# radiata_v2.net
KiCad netlist of a schematic drawn in EAGLE
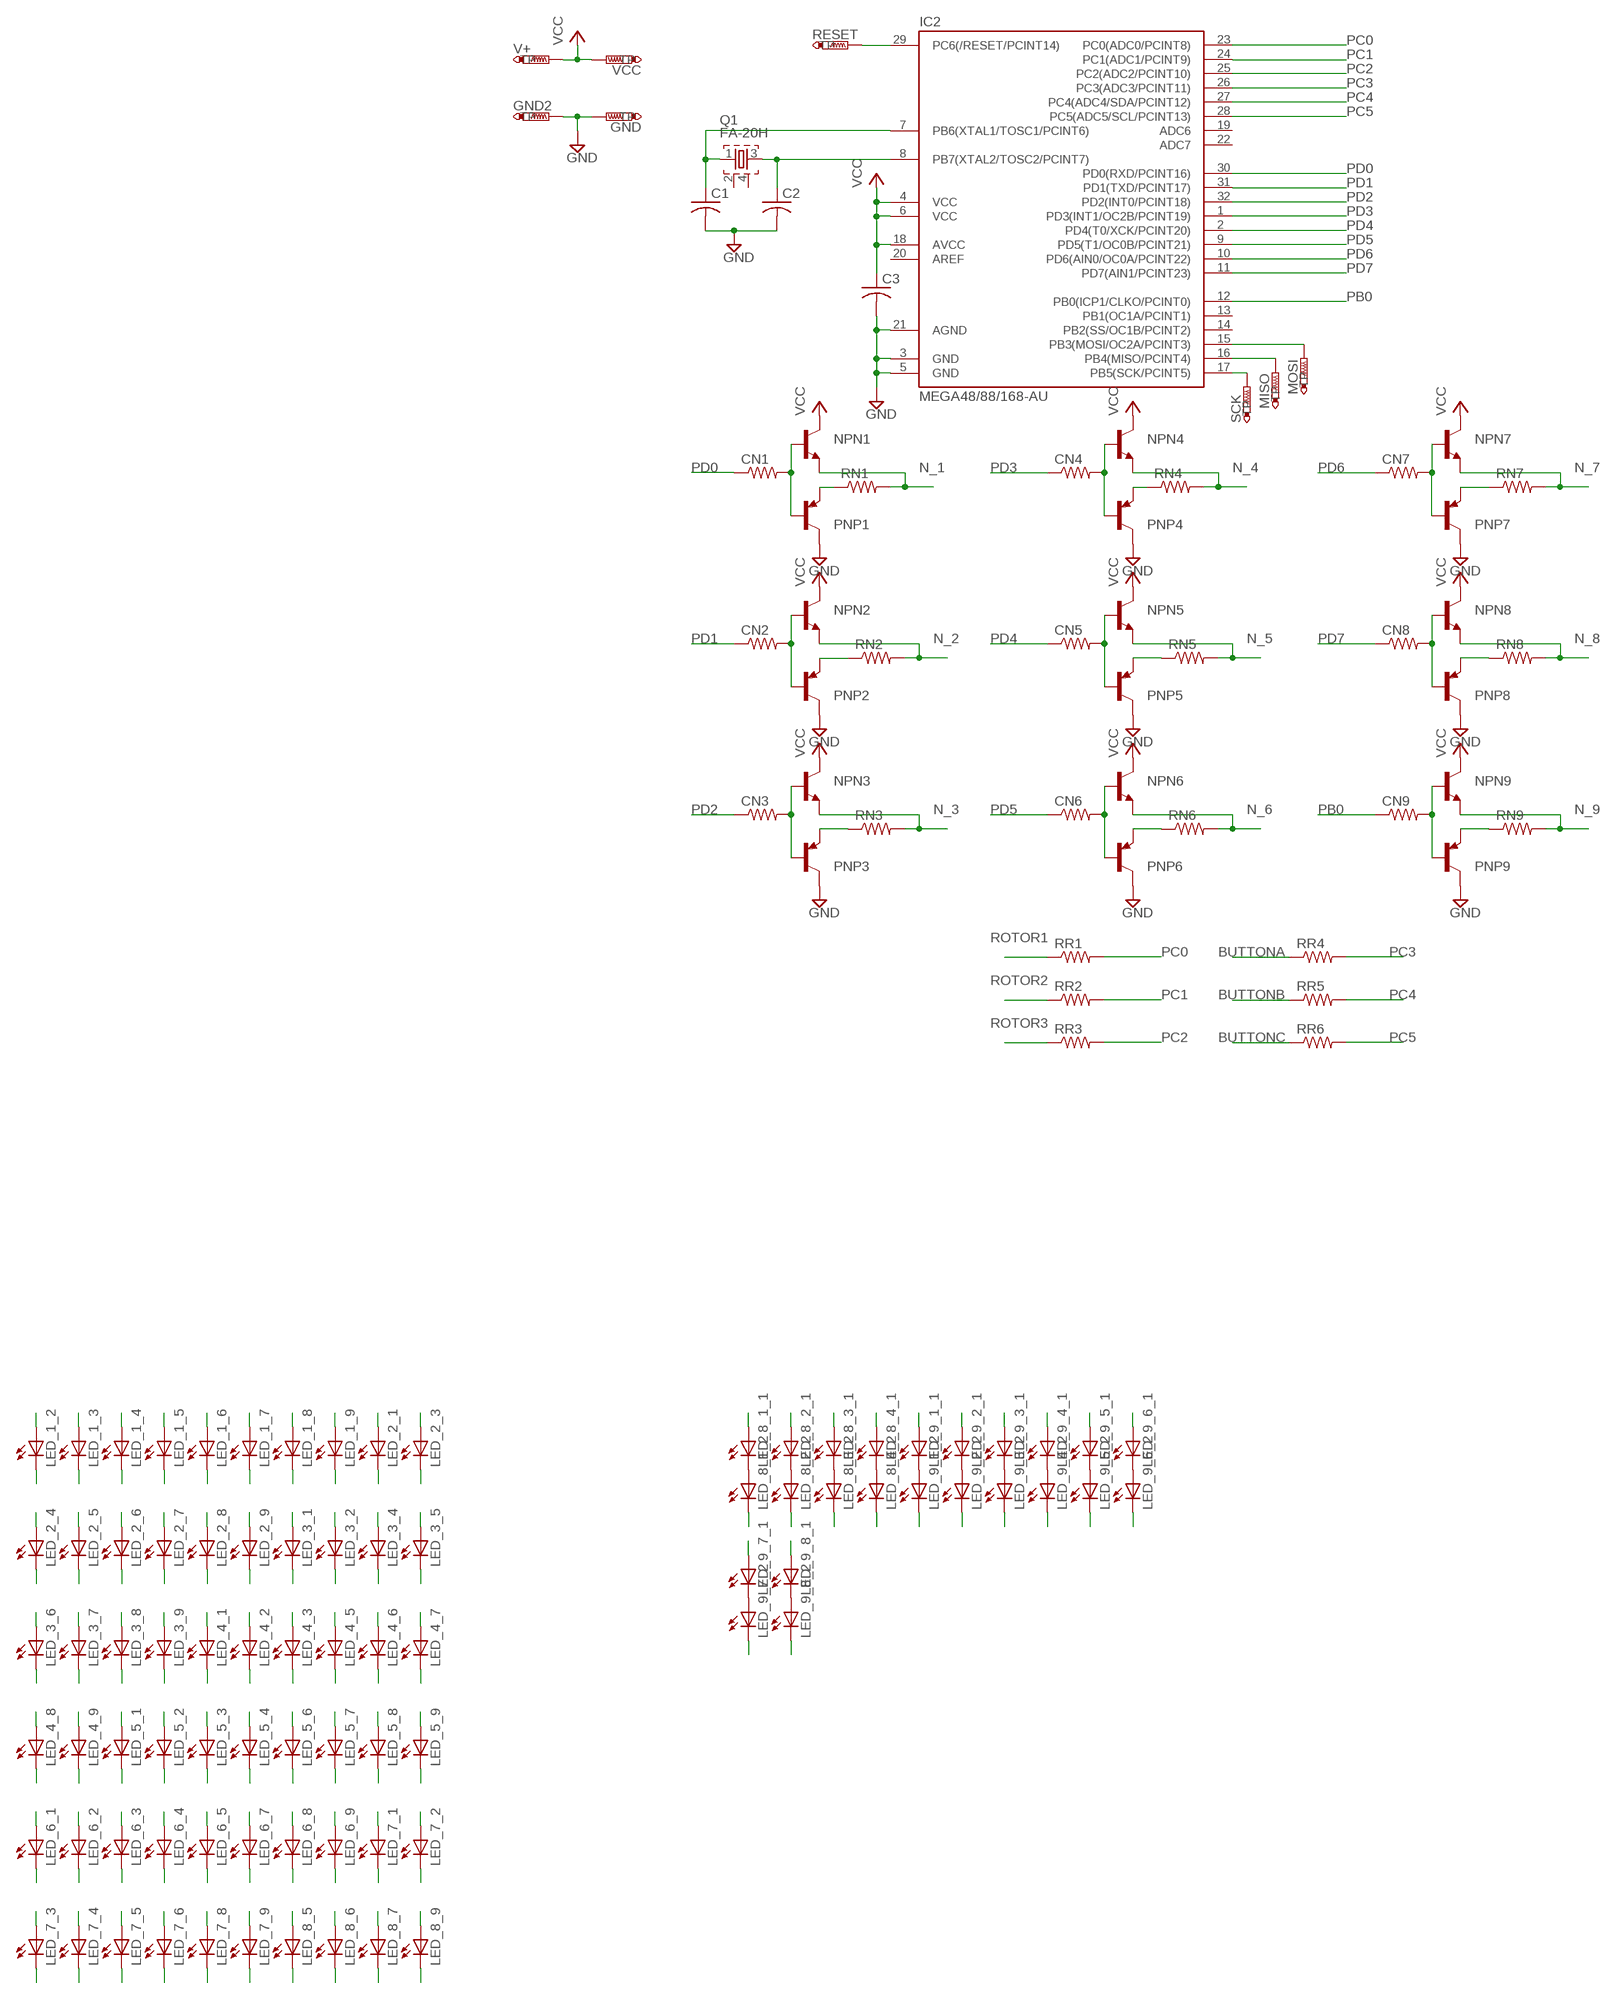
[diagram p0: schematic, sheet 1]

(export (version "E")
  (design (tool "Eeschema 10.0.6"))
  (components
    (comp (ref "C1")
      (value "C-USC0603")
      (footprint "eagle-import:C0603")
      (libsource (lib "eagle-import") (part "C-USC0603"))
    )
    (comp (ref "C2")
      (value "C-USC0603")
      (footprint "eagle-import:C0603")
      (libsource (lib "eagle-import") (part "C-USC0603"))
    )
    (comp (ref "C3")
      (value "C-USC0603")
      (footprint "eagle-import:C0603")
      (libsource (lib "eagle-import") (part "C-USC0603"))
    )
    (comp (ref "CN1")
      (value "R-US_M0805")
      (footprint "eagle-import:M0805")
      (libsource (lib "eagle-import") (part "R-US_M0805"))
    )
    (comp (ref "CN2")
      (value "R-US_M0805")
      (footprint "eagle-import:M0805")
      (libsource (lib "eagle-import") (part "R-US_M0805"))
    )
    (comp (ref "CN3")
      (value "R-US_M0805")
      (footprint "eagle-import:M0805")
      (libsource (lib "eagle-import") (part "R-US_M0805"))
    )
    (comp (ref "CN4")
      (value "R-US_M0805")
      (footprint "eagle-import:M0805")
      (libsource (lib "eagle-import") (part "R-US_M0805"))
    )
    (comp (ref "CN5")
      (value "R-US_M0805")
      (footprint "eagle-import:M0805")
      (libsource (lib "eagle-import") (part "R-US_M0805"))
    )
    (comp (ref "CN6")
      (value "R-US_M0805")
      (footprint "eagle-import:M0805")
      (libsource (lib "eagle-import") (part "R-US_M0805"))
    )
    (comp (ref "CN7")
      (value "R-US_M0805")
      (footprint "eagle-import:M0805")
      (libsource (lib "eagle-import") (part "R-US_M0805"))
    )
    (comp (ref "CN8")
      (value "R-US_M0805")
      (footprint "eagle-import:M0805")
      (libsource (lib "eagle-import") (part "R-US_M0805"))
    )
    (comp (ref "CN9")
      (value "R-US_M0805")
      (footprint "eagle-import:M0805")
      (libsource (lib "eagle-import") (part "R-US_M0805"))
    )
    (comp (ref "GND")
      (value "PTR1TP19R")
      (footprint "eagle-import:TP19R")
      (libsource (lib "eagle-import") (part "PTR1TP19R"))
    )
    (comp (ref "GND2")
      (value "PTR1TP20SQ")
      (footprint "eagle-import:TP20SQ")
      (libsource (lib "eagle-import") (part "PTR1TP20SQ"))
    )
    (comp (ref "IC2")
      (value "MEGA48/88/168-AU")
      (footprint "eagle-import:TQFP32-08")
      (libsource (lib "eagle-import") (part "MEGA48/88/168-AU"))
    )
    (comp (ref "LED_1_2")
      (value "LED1206")
      (footprint "eagle-import:LED-1206")
      (libsource (lib "eagle-import") (part "LED1206"))
    )
    (comp (ref "LED_1_3")
      (value "LED1206")
      (footprint "eagle-import:LED-1206")
      (libsource (lib "eagle-import") (part "LED1206"))
    )
    (comp (ref "LED_1_4")
      (value "LED1206")
      (footprint "eagle-import:LED-1206")
      (libsource (lib "eagle-import") (part "LED1206"))
    )
    (comp (ref "LED_1_5")
      (value "LED1206")
      (footprint "eagle-import:LED-1206")
      (libsource (lib "eagle-import") (part "LED1206"))
    )
    (comp (ref "LED_1_6")
      (value "LED1206")
      (footprint "eagle-import:LED-1206")
      (libsource (lib "eagle-import") (part "LED1206"))
    )
    (comp (ref "LED_1_7")
      (value "LED1206")
      (footprint "eagle-import:LED-1206")
      (libsource (lib "eagle-import") (part "LED1206"))
    )
    (comp (ref "LED_1_8")
      (value "LED1206")
      (footprint "eagle-import:LED-1206")
      (libsource (lib "eagle-import") (part "LED1206"))
    )
    (comp (ref "LED_1_9")
      (value "LED1206")
      (footprint "eagle-import:LED-1206")
      (libsource (lib "eagle-import") (part "LED1206"))
    )
    (comp (ref "LED_2_1")
      (value "LED1206")
      (footprint "eagle-import:LED-1206")
      (libsource (lib "eagle-import") (part "LED1206"))
    )
    (comp (ref "LED_2_3")
      (value "LED1206")
      (footprint "eagle-import:LED-1206")
      (libsource (lib "eagle-import") (part "LED1206"))
    )
    (comp (ref "LED_2_4")
      (value "LED1206")
      (footprint "eagle-import:LED-1206")
      (libsource (lib "eagle-import") (part "LED1206"))
    )
    (comp (ref "LED_2_5")
      (value "LED1206")
      (footprint "eagle-import:LED-1206")
      (libsource (lib "eagle-import") (part "LED1206"))
    )
    (comp (ref "LED_2_6")
      (value "LED1206")
      (footprint "eagle-import:LED-1206")
      (libsource (lib "eagle-import") (part "LED1206"))
    )
    (comp (ref "LED_2_7")
      (value "LED1206")
      (footprint "eagle-import:LED-1206")
      (libsource (lib "eagle-import") (part "LED1206"))
    )
    (comp (ref "LED_2_8")
      (value "LED1206")
      (footprint "eagle-import:LED-1206")
      (libsource (lib "eagle-import") (part "LED1206"))
    )
    (comp (ref "LED_2_9")
      (value "LED1206")
      (footprint "eagle-import:LED-1206")
      (libsource (lib "eagle-import") (part "LED1206"))
    )
    (comp (ref "LED_3_1")
      (value "LED1206")
      (footprint "eagle-import:LED-1206")
      (libsource (lib "eagle-import") (part "LED1206"))
    )
    (comp (ref "LED_3_2")
      (value "LED1206")
      (footprint "eagle-import:LED-1206")
      (libsource (lib "eagle-import") (part "LED1206"))
    )
    (comp (ref "LED_3_4")
      (value "LED1206")
      (footprint "eagle-import:LED-1206")
      (libsource (lib "eagle-import") (part "LED1206"))
    )
    (comp (ref "LED_3_5")
      (value "LED1206")
      (footprint "eagle-import:LED-1206")
      (libsource (lib "eagle-import") (part "LED1206"))
    )
    (comp (ref "LED_3_6")
      (value "LED1206")
      (footprint "eagle-import:LED-1206")
      (libsource (lib "eagle-import") (part "LED1206"))
    )
    (comp (ref "LED_3_7")
      (value "LED1206")
      (footprint "eagle-import:LED-1206")
      (libsource (lib "eagle-import") (part "LED1206"))
    )
    (comp (ref "LED_3_8")
      (value "LED1206")
      (footprint "eagle-import:LED-1206")
      (libsource (lib "eagle-import") (part "LED1206"))
    )
    (comp (ref "LED_3_9")
      (value "LED1206")
      (footprint "eagle-import:LED-1206")
      (libsource (lib "eagle-import") (part "LED1206"))
    )
    (comp (ref "LED_4_1")
      (value "LED1206")
      (footprint "eagle-import:LED-1206")
      (libsource (lib "eagle-import") (part "LED1206"))
    )
    (comp (ref "LED_4_2")
      (value "LED1206")
      (footprint "eagle-import:LED-1206")
      (libsource (lib "eagle-import") (part "LED1206"))
    )
    (comp (ref "LED_4_3")
      (value "LED1206")
      (footprint "eagle-import:LED-1206")
      (libsource (lib "eagle-import") (part "LED1206"))
    )
    (comp (ref "LED_4_5")
      (value "LED1206")
      (footprint "eagle-import:LED-1206")
      (libsource (lib "eagle-import") (part "LED1206"))
    )
    (comp (ref "LED_4_6")
      (value "LED1206")
      (footprint "eagle-import:LED-1206")
      (libsource (lib "eagle-import") (part "LED1206"))
    )
    (comp (ref "LED_4_7")
      (value "LED1206")
      (footprint "eagle-import:LED-1206")
      (libsource (lib "eagle-import") (part "LED1206"))
    )
    (comp (ref "LED_4_8")
      (value "LED1206")
      (footprint "eagle-import:LED-1206")
      (libsource (lib "eagle-import") (part "LED1206"))
    )
    (comp (ref "LED_4_9")
      (value "LED1206")
      (footprint "eagle-import:LED-1206")
      (libsource (lib "eagle-import") (part "LED1206"))
    )
    (comp (ref "LED_5_1")
      (value "LED1206")
      (footprint "eagle-import:LED-1206")
      (libsource (lib "eagle-import") (part "LED1206"))
    )
    (comp (ref "LED_5_2")
      (value "LED1206")
      (footprint "eagle-import:LED-1206")
      (libsource (lib "eagle-import") (part "LED1206"))
    )
    (comp (ref "LED_5_3")
      (value "LED1206")
      (footprint "eagle-import:LED-1206")
      (libsource (lib "eagle-import") (part "LED1206"))
    )
    (comp (ref "LED_5_4")
      (value "LED1206")
      (footprint "eagle-import:LED-1206")
      (libsource (lib "eagle-import") (part "LED1206"))
    )
    (comp (ref "LED_5_6")
      (value "LED1206")
      (footprint "eagle-import:LED-1206")
      (libsource (lib "eagle-import") (part "LED1206"))
    )
    (comp (ref "LED_5_7")
      (value "LED1206")
      (footprint "eagle-import:LED-1206")
      (libsource (lib "eagle-import") (part "LED1206"))
    )
    (comp (ref "LED_5_8")
      (value "LED1206")
      (footprint "eagle-import:LED-1206")
      (libsource (lib "eagle-import") (part "LED1206"))
    )
    (comp (ref "LED_5_9")
      (value "LED1206")
      (footprint "eagle-import:LED-1206")
      (libsource (lib "eagle-import") (part "LED1206"))
    )
    (comp (ref "LED_6_1")
      (value "LED1206")
      (footprint "eagle-import:LED-1206")
      (libsource (lib "eagle-import") (part "LED1206"))
    )
    (comp (ref "LED_6_2")
      (value "LED1206")
      (footprint "eagle-import:LED-1206")
      (libsource (lib "eagle-import") (part "LED1206"))
    )
    (comp (ref "LED_6_3")
      (value "LED1206")
      (footprint "eagle-import:LED-1206")
      (libsource (lib "eagle-import") (part "LED1206"))
    )
    (comp (ref "LED_6_4")
      (value "LED1206")
      (footprint "eagle-import:LED-1206")
      (libsource (lib "eagle-import") (part "LED1206"))
    )
    (comp (ref "LED_6_5")
      (value "LED1206")
      (footprint "eagle-import:LED-1206")
      (libsource (lib "eagle-import") (part "LED1206"))
    )
    (comp (ref "LED_6_7")
      (value "LED1206")
      (footprint "eagle-import:LED-1206")
      (libsource (lib "eagle-import") (part "LED1206"))
    )
    (comp (ref "LED_6_8")
      (value "LED1206")
      (footprint "eagle-import:LED-1206")
      (libsource (lib "eagle-import") (part "LED1206"))
    )
    (comp (ref "LED_6_9")
      (value "LED1206")
      (footprint "eagle-import:LED-1206")
      (libsource (lib "eagle-import") (part "LED1206"))
    )
    (comp (ref "LED_7_1")
      (value "LED1206")
      (footprint "eagle-import:LED-1206")
      (libsource (lib "eagle-import") (part "LED1206"))
    )
    (comp (ref "LED_7_2")
      (value "LED1206")
      (footprint "eagle-import:LED-1206")
      (libsource (lib "eagle-import") (part "LED1206"))
    )
    (comp (ref "LED_7_3")
      (value "LED1206")
      (footprint "eagle-import:LED-1206")
      (libsource (lib "eagle-import") (part "LED1206"))
    )
    (comp (ref "LED_7_4")
      (value "LED1206")
      (footprint "eagle-import:LED-1206")
      (libsource (lib "eagle-import") (part "LED1206"))
    )
    (comp (ref "LED_7_5")
      (value "LED1206")
      (footprint "eagle-import:LED-1206")
      (libsource (lib "eagle-import") (part "LED1206"))
    )
    (comp (ref "LED_7_6")
      (value "LED1206")
      (footprint "eagle-import:LED-1206")
      (libsource (lib "eagle-import") (part "LED1206"))
    )
    (comp (ref "LED_7_8")
      (value "LED1206")
      (footprint "eagle-import:LED-1206")
      (libsource (lib "eagle-import") (part "LED1206"))
    )
    (comp (ref "LED_7_9")
      (value "LED1206")
      (footprint "eagle-import:LED-1206")
      (libsource (lib "eagle-import") (part "LED1206"))
    )
    (comp (ref "LED_8_1_1")
      (value "LED1206")
      (footprint "eagle-import:LED-1206")
      (libsource (lib "eagle-import") (part "LED1206"))
    )
    (comp (ref "LED_8_1_2")
      (value "LED1206")
      (footprint "eagle-import:LED-1206")
      (libsource (lib "eagle-import") (part "LED1206"))
    )
    (comp (ref "LED_8_2_1")
      (value "LED1206")
      (footprint "eagle-import:LED-1206")
      (libsource (lib "eagle-import") (part "LED1206"))
    )
    (comp (ref "LED_8_2_2")
      (value "LED1206")
      (footprint "eagle-import:LED-1206")
      (libsource (lib "eagle-import") (part "LED1206"))
    )
    (comp (ref "LED_8_3_1")
      (value "LED1206")
      (footprint "eagle-import:LED-1206")
      (libsource (lib "eagle-import") (part "LED1206"))
    )
    (comp (ref "LED_8_3_2")
      (value "LED1206")
      (footprint "eagle-import:LED-1206")
      (libsource (lib "eagle-import") (part "LED1206"))
    )
    (comp (ref "LED_8_4_1")
      (value "LED1206")
      (footprint "eagle-import:LED-1206")
      (libsource (lib "eagle-import") (part "LED1206"))
    )
    (comp (ref "LED_8_4_2")
      (value "LED1206")
      (footprint "eagle-import:LED-1206")
      (libsource (lib "eagle-import") (part "LED1206"))
    )
    (comp (ref "LED_8_5")
      (value "LED1206")
      (footprint "eagle-import:LED-1206")
      (libsource (lib "eagle-import") (part "LED1206"))
    )
    (comp (ref "LED_8_6")
      (value "LED1206")
      (footprint "eagle-import:LED-1206")
      (libsource (lib "eagle-import") (part "LED1206"))
    )
    (comp (ref "LED_8_7")
      (value "LED1206")
      (footprint "eagle-import:LED-1206")
      (libsource (lib "eagle-import") (part "LED1206"))
    )
    (comp (ref "LED_8_9")
      (value "LED1206")
      (footprint "eagle-import:LED-1206")
      (libsource (lib "eagle-import") (part "LED1206"))
    )
    (comp (ref "LED_9_1_1")
      (value "LED1206")
      (footprint "eagle-import:LED-1206")
      (libsource (lib "eagle-import") (part "LED1206"))
    )
    (comp (ref "LED_9_1_2")
      (value "LED1206")
      (footprint "eagle-import:LED-1206")
      (libsource (lib "eagle-import") (part "LED1206"))
    )
    (comp (ref "LED_9_2_1")
      (value "LED1206")
      (footprint "eagle-import:LED-1206")
      (libsource (lib "eagle-import") (part "LED1206"))
    )
    (comp (ref "LED_9_2_2")
      (value "LED1206")
      (footprint "eagle-import:LED-1206")
      (libsource (lib "eagle-import") (part "LED1206"))
    )
    (comp (ref "LED_9_3_1")
      (value "LED1206")
      (footprint "eagle-import:LED-1206")
      (libsource (lib "eagle-import") (part "LED1206"))
    )
    (comp (ref "LED_9_3_2")
      (value "LED1206")
      (footprint "eagle-import:LED-1206")
      (libsource (lib "eagle-import") (part "LED1206"))
    )
    (comp (ref "LED_9_4_1")
      (value "LED1206")
      (footprint "eagle-import:LED-1206")
      (libsource (lib "eagle-import") (part "LED1206"))
    )
    (comp (ref "LED_9_4_2")
      (value "LED1206")
      (footprint "eagle-import:LED-1206")
      (libsource (lib "eagle-import") (part "LED1206"))
    )
    (comp (ref "LED_9_5_1")
      (value "LED1206")
      (footprint "eagle-import:LED-1206")
      (libsource (lib "eagle-import") (part "LED1206"))
    )
    (comp (ref "LED_9_5_2")
      (value "LED1206")
      (footprint "eagle-import:LED-1206")
      (libsource (lib "eagle-import") (part "LED1206"))
    )
    (comp (ref "LED_9_6_1")
      (value "LED1206")
      (footprint "eagle-import:LED-1206")
      (libsource (lib "eagle-import") (part "LED1206"))
    )
    (comp (ref "LED_9_6_2")
      (value "LED1206")
      (footprint "eagle-import:LED-1206")
      (libsource (lib "eagle-import") (part "LED1206"))
    )
    (comp (ref "LED_9_7_1")
      (value "LED1206")
      (footprint "eagle-import:LED-1206")
      (libsource (lib "eagle-import") (part "LED1206"))
    )
    (comp (ref "LED_9_7_2")
      (value "LED1206")
      (footprint "eagle-import:LED-1206")
      (libsource (lib "eagle-import") (part "LED1206"))
    )
    (comp (ref "LED_9_8_1")
      (value "LED1206")
      (footprint "eagle-import:LED-1206")
      (libsource (lib "eagle-import") (part "LED1206"))
    )
    (comp (ref "LED_9_8_2")
      (value "LED1206")
      (footprint "eagle-import:LED-1206")
      (libsource (lib "eagle-import") (part "LED1206"))
    )
    (comp (ref "MISO")
      (value "PTR1TP19R")
      (footprint "eagle-import:TP19R")
      (libsource (lib "eagle-import") (part "PTR1TP19R"))
    )
    (comp (ref "MOSI")
      (value "PTR1TP19R")
      (footprint "eagle-import:TP19R")
      (libsource (lib "eagle-import") (part "PTR1TP19R"))
    )
    (comp (ref "NPN1")
      (value "MMBT2222ALT1-NPN-SOT23-BEC")
      (footprint "eagle-import:SOT23-BEC")
      (libsource (lib "eagle-import") (part "-NPN-SOT23-BECMMBT2222ALT1"))
    )
    (comp (ref "NPN2")
      (value "MMBT2222ALT1-NPN-SOT23-BEC")
      (footprint "eagle-import:SOT23-BEC")
      (libsource (lib "eagle-import") (part "-NPN-SOT23-BECMMBT2222ALT1"))
    )
    (comp (ref "NPN3")
      (value "MMBT2222ALT1-NPN-SOT23-BEC")
      (footprint "eagle-import:SOT23-BEC")
      (libsource (lib "eagle-import") (part "-NPN-SOT23-BECMMBT2222ALT1"))
    )
    (comp (ref "NPN4")
      (value "MMBT2222ALT1-NPN-SOT23-BEC")
      (footprint "eagle-import:SOT23-BEC")
      (libsource (lib "eagle-import") (part "-NPN-SOT23-BECMMBT2222ALT1"))
    )
    (comp (ref "NPN5")
      (value "MMBT2222ALT1-NPN-SOT23-BEC")
      (footprint "eagle-import:SOT23-BEC")
      (libsource (lib "eagle-import") (part "-NPN-SOT23-BECMMBT2222ALT1"))
    )
    (comp (ref "NPN6")
      (value "MMBT2222ALT1-NPN-SOT23-BEC")
      (footprint "eagle-import:SOT23-BEC")
      (libsource (lib "eagle-import") (part "-NPN-SOT23-BECMMBT2222ALT1"))
    )
    (comp (ref "NPN7")
      (value "MMBT2222ALT1-NPN-SOT23-BEC")
      (footprint "eagle-import:SOT23-BEC")
      (libsource (lib "eagle-import") (part "-NPN-SOT23-BECMMBT2222ALT1"))
    )
    (comp (ref "NPN8")
      (value "MMBT2222ALT1-NPN-SOT23-BEC")
      (footprint "eagle-import:SOT23-BEC")
      (libsource (lib "eagle-import") (part "-NPN-SOT23-BECMMBT2222ALT1"))
    )
    (comp (ref "NPN9")
      (value "MMBT2222ALT1-NPN-SOT23-BEC")
      (footprint "eagle-import:SOT23-BEC")
      (libsource (lib "eagle-import") (part "-NPN-SOT23-BECMMBT2222ALT1"))
    )
    (comp (ref "PNP1")
      (value "MMBT2907ALT1-PNP-SOT23-BEC")
      (footprint "eagle-import:SOT23-BEC")
      (libsource (lib "eagle-import") (part "-PNP-SOT23-BECMMBT2907ALT1"))
    )
    (comp (ref "PNP2")
      (value "MMBT2907ALT1-PNP-SOT23-BEC")
      (footprint "eagle-import:SOT23-BEC")
      (libsource (lib "eagle-import") (part "-PNP-SOT23-BECMMBT2907ALT1"))
    )
    (comp (ref "PNP3")
      (value "MMBT2907ALT1-PNP-SOT23-BEC")
      (footprint "eagle-import:SOT23-BEC")
      (libsource (lib "eagle-import") (part "-PNP-SOT23-BECMMBT2907ALT1"))
    )
    (comp (ref "PNP4")
      (value "MMBT2907ALT1-PNP-SOT23-BEC")
      (footprint "eagle-import:SOT23-BEC")
      (libsource (lib "eagle-import") (part "-PNP-SOT23-BECMMBT2907ALT1"))
    )
    (comp (ref "PNP5")
      (value "MMBT2907ALT1-PNP-SOT23-BEC")
      (footprint "eagle-import:SOT23-BEC")
      (libsource (lib "eagle-import") (part "-PNP-SOT23-BECMMBT2907ALT1"))
    )
    (comp (ref "PNP6")
      (value "MMBT2907ALT1-PNP-SOT23-BEC")
      (footprint "eagle-import:SOT23-BEC")
      (libsource (lib "eagle-import") (part "-PNP-SOT23-BECMMBT2907ALT1"))
    )
    (comp (ref "PNP7")
      (value "MMBT2907ALT1-PNP-SOT23-BEC")
      (footprint "eagle-import:SOT23-BEC")
      (libsource (lib "eagle-import") (part "-PNP-SOT23-BECMMBT2907ALT1"))
    )
    (comp (ref "PNP8")
      (value "MMBT2907ALT1-PNP-SOT23-BEC")
      (footprint "eagle-import:SOT23-BEC")
      (libsource (lib "eagle-import") (part "-PNP-SOT23-BECMMBT2907ALT1"))
    )
    (comp (ref "PNP9")
      (value "MMBT2907ALT1-PNP-SOT23-BEC")
      (footprint "eagle-import:SOT23-BEC")
      (libsource (lib "eagle-import") (part "-PNP-SOT23-BECMMBT2907ALT1"))
    )
    (comp (ref "Q1")
      (value "FA-20H")
      (footprint "eagle-import:FA-20H")
      (libsource (lib "eagle-import") (part "FA-20H"))
    )
    (comp (ref "RESET")
      (value "PTR1TP19R")
      (footprint "eagle-import:TP19R")
      (libsource (lib "eagle-import") (part "PTR1TP19R"))
    )
    (comp (ref "RN1")
      (value "RESISTOR1206")
      (footprint "eagle-import:1206")
      (libsource (lib "eagle-import") (part "RESISTOR1206"))
    )
    (comp (ref "RN2")
      (value "RESISTOR1206")
      (footprint "eagle-import:1206")
      (libsource (lib "eagle-import") (part "RESISTOR1206"))
    )
    (comp (ref "RN3")
      (value "RESISTOR1206")
      (footprint "eagle-import:1206")
      (libsource (lib "eagle-import") (part "RESISTOR1206"))
    )
    (comp (ref "RN4")
      (value "RESISTOR1206")
      (footprint "eagle-import:1206")
      (libsource (lib "eagle-import") (part "RESISTOR1206"))
    )
    (comp (ref "RN5")
      (value "RESISTOR1206")
      (footprint "eagle-import:1206")
      (libsource (lib "eagle-import") (part "RESISTOR1206"))
    )
    (comp (ref "RN6")
      (value "RESISTOR1206")
      (footprint "eagle-import:1206")
      (libsource (lib "eagle-import") (part "RESISTOR1206"))
    )
    (comp (ref "RN7")
      (value "RESISTOR1206")
      (footprint "eagle-import:1206")
      (libsource (lib "eagle-import") (part "RESISTOR1206"))
    )
    (comp (ref "RN8")
      (value "RESISTOR1206")
      (footprint "eagle-import:1206")
      (libsource (lib "eagle-import") (part "RESISTOR1206"))
    )
    (comp (ref "RN9")
      (value "RESISTOR1206")
      (footprint "eagle-import:1206")
      (libsource (lib "eagle-import") (part "RESISTOR1206"))
    )
    (comp (ref "RR1")
      (value "RESISTOR1206")
      (footprint "eagle-import:1206")
      (libsource (lib "eagle-import") (part "RESISTOR1206"))
    )
    (comp (ref "RR2")
      (value "RESISTOR1206")
      (footprint "eagle-import:1206")
      (libsource (lib "eagle-import") (part "RESISTOR1206"))
    )
    (comp (ref "RR3")
      (value "RESISTOR1206")
      (footprint "eagle-import:1206")
      (libsource (lib "eagle-import") (part "RESISTOR1206"))
    )
    (comp (ref "RR4")
      (value "RESISTOR1206")
      (footprint "eagle-import:1206")
      (libsource (lib "eagle-import") (part "RESISTOR1206"))
    )
    (comp (ref "RR5")
      (value "RESISTOR1206")
      (footprint "eagle-import:1206")
      (libsource (lib "eagle-import") (part "RESISTOR1206"))
    )
    (comp (ref "RR6")
      (value "RESISTOR1206")
      (footprint "eagle-import:1206")
      (libsource (lib "eagle-import") (part "RESISTOR1206"))
    )
    (comp (ref "SCK")
      (value "PTR1TP19R")
      (footprint "eagle-import:TP19R")
      (libsource (lib "eagle-import") (part "PTR1TP19R"))
    )
    (comp (ref "V+")
      (value "PTR1TP20SQ")
      (footprint "eagle-import:TP20SQ")
      (libsource (lib "eagle-import") (part "PTR1TP20SQ"))
    )
    (comp (ref "VCC")
      (value "PTR1TP19R")
      (footprint "eagle-import:TP19R")
      (libsource (lib "eagle-import") (part "PTR1TP19R"))
    )
  )
  (nets
    (net (code "1") (name "/BUTTONA") (class "Default")
      (node (ref "RR4") (pin "1") (pinfunction "1_1") (pintype "passive"))
    )
    (net (code "2") (name "/BUTTONB") (class "Default")
      (node (ref "RR5") (pin "1") (pinfunction "1_1") (pintype "passive"))
    )
    (net (code "3") (name "/BUTTONC") (class "Default")
      (node (ref "RR6") (pin "1") (pinfunction "1_1") (pintype "passive"))
    )
    (net (code "4") (name "/N_1") (class "Default")
      (node (ref "LED_1_2") (pin "A") (pinfunction "A_A") (pintype "passive"))
      (node (ref "LED_1_3") (pin "A") (pinfunction "A_A") (pintype "passive"))
      (node (ref "LED_1_4") (pin "A") (pinfunction "A_A") (pintype "passive"))
      (node (ref "LED_1_5") (pin "A") (pinfunction "A_A") (pintype "passive"))
      (node (ref "LED_1_6") (pin "A") (pinfunction "A_A") (pintype "passive"))
      (node (ref "LED_1_7") (pin "A") (pinfunction "A_A") (pintype "passive"))
      (node (ref "LED_1_8") (pin "A") (pinfunction "A_A") (pintype "passive"))
      (node (ref "LED_1_9") (pin "A") (pinfunction "A_A") (pintype "passive"))
      (node (ref "LED_2_1") (pin "C") (pinfunction "C_C") (pintype "passive"))
      (node (ref "LED_3_1") (pin "C") (pinfunction "C_C") (pintype "passive"))
      (node (ref "LED_4_1") (pin "C") (pinfunction "C_C") (pintype "passive"))
      (node (ref "LED_5_1") (pin "C") (pinfunction "C_C") (pintype "passive"))
      (node (ref "LED_6_1") (pin "C") (pinfunction "C_C") (pintype "passive"))
      (node (ref "LED_7_1") (pin "C") (pinfunction "C_C") (pintype "passive"))
      (node (ref "LED_8_1_2") (pin "C") (pinfunction "C_C") (pintype "passive"))
      (node (ref "LED_9_1_2") (pin "C") (pinfunction "C_C") (pintype "passive"))
      (node (ref "NPN1") (pin "E") (pinfunction "E_E") (pintype "passive"))
      (node (ref "RN1") (pin "2") (pinfunction "2_2") (pintype "passive"))
    )
    (net (code "5") (name "/N_2") (class "Default")
      (node (ref "LED_1_2") (pin "C") (pinfunction "C_C") (pintype "passive"))
      (node (ref "LED_2_1") (pin "A") (pinfunction "A_A") (pintype "passive"))
      (node (ref "LED_2_3") (pin "A") (pinfunction "A_A") (pintype "passive"))
      (node (ref "LED_2_4") (pin "A") (pinfunction "A_A") (pintype "passive"))
      (node (ref "LED_2_5") (pin "A") (pinfunction "A_A") (pintype "passive"))
      (node (ref "LED_2_6") (pin "A") (pinfunction "A_A") (pintype "passive"))
      (node (ref "LED_2_7") (pin "A") (pinfunction "A_A") (pintype "passive"))
      (node (ref "LED_2_8") (pin "A") (pinfunction "A_A") (pintype "passive"))
      (node (ref "LED_2_9") (pin "A") (pinfunction "A_A") (pintype "passive"))
      (node (ref "LED_3_2") (pin "C") (pinfunction "C_C") (pintype "passive"))
      (node (ref "LED_4_2") (pin "C") (pinfunction "C_C") (pintype "passive"))
      (node (ref "LED_5_2") (pin "C") (pinfunction "C_C") (pintype "passive"))
      (node (ref "LED_6_2") (pin "C") (pinfunction "C_C") (pintype "passive"))
      (node (ref "LED_7_2") (pin "C") (pinfunction "C_C") (pintype "passive"))
      (node (ref "LED_8_2_2") (pin "C") (pinfunction "C_C") (pintype "passive"))
      (node (ref "LED_9_2_2") (pin "C") (pinfunction "C_C") (pintype "passive"))
      (node (ref "NPN2") (pin "E") (pinfunction "E_E") (pintype "passive"))
      (node (ref "RN2") (pin "2") (pinfunction "2_2") (pintype "passive"))
    )
    (net (code "6") (name "/N_3") (class "Default")
      (node (ref "LED_1_3") (pin "C") (pinfunction "C_C") (pintype "passive"))
      (node (ref "LED_2_3") (pin "C") (pinfunction "C_C") (pintype "passive"))
      (node (ref "LED_3_1") (pin "A") (pinfunction "A_A") (pintype "passive"))
      (node (ref "LED_3_2") (pin "A") (pinfunction "A_A") (pintype "passive"))
      (node (ref "LED_3_4") (pin "A") (pinfunction "A_A") (pintype "passive"))
      (node (ref "LED_3_5") (pin "A") (pinfunction "A_A") (pintype "passive"))
      (node (ref "LED_3_6") (pin "A") (pinfunction "A_A") (pintype "passive"))
      (node (ref "LED_3_7") (pin "A") (pinfunction "A_A") (pintype "passive"))
      (node (ref "LED_3_8") (pin "A") (pinfunction "A_A") (pintype "passive"))
      (node (ref "LED_3_9") (pin "A") (pinfunction "A_A") (pintype "passive"))
      (node (ref "LED_4_3") (pin "C") (pinfunction "C_C") (pintype "passive"))
      (node (ref "LED_5_3") (pin "C") (pinfunction "C_C") (pintype "passive"))
      (node (ref "LED_6_3") (pin "C") (pinfunction "C_C") (pintype "passive"))
      (node (ref "LED_7_3") (pin "C") (pinfunction "C_C") (pintype "passive"))
      (node (ref "LED_8_3_2") (pin "C") (pinfunction "C_C") (pintype "passive"))
      (node (ref "LED_9_3_2") (pin "C") (pinfunction "C_C") (pintype "passive"))
      (node (ref "NPN3") (pin "E") (pinfunction "E_E") (pintype "passive"))
      (node (ref "RN3") (pin "2") (pinfunction "2_2") (pintype "passive"))
    )
    (net (code "7") (name "/N_4") (class "Default")
      (node (ref "LED_1_4") (pin "C") (pinfunction "C_C") (pintype "passive"))
      (node (ref "LED_2_4") (pin "C") (pinfunction "C_C") (pintype "passive"))
      (node (ref "LED_3_4") (pin "C") (pinfunction "C_C") (pintype "passive"))
      (node (ref "LED_4_1") (pin "A") (pinfunction "A_A") (pintype "passive"))
      (node (ref "LED_4_2") (pin "A") (pinfunction "A_A") (pintype "passive"))
      (node (ref "LED_4_3") (pin "A") (pinfunction "A_A") (pintype "passive"))
      (node (ref "LED_4_5") (pin "A") (pinfunction "A_A") (pintype "passive"))
      (node (ref "LED_4_6") (pin "A") (pinfunction "A_A") (pintype "passive"))
      (node (ref "LED_4_7") (pin "A") (pinfunction "A_A") (pintype "passive"))
      (node (ref "LED_4_8") (pin "A") (pinfunction "A_A") (pintype "passive"))
      (node (ref "LED_4_9") (pin "A") (pinfunction "A_A") (pintype "passive"))
      (node (ref "LED_5_4") (pin "C") (pinfunction "C_C") (pintype "passive"))
      (node (ref "LED_6_4") (pin "C") (pinfunction "C_C") (pintype "passive"))
      (node (ref "LED_7_4") (pin "C") (pinfunction "C_C") (pintype "passive"))
      (node (ref "LED_8_4_2") (pin "C") (pinfunction "C_C") (pintype "passive"))
      (node (ref "LED_9_4_2") (pin "C") (pinfunction "C_C") (pintype "passive"))
      (node (ref "NPN4") (pin "E") (pinfunction "E_E") (pintype "passive"))
      (node (ref "RN4") (pin "2") (pinfunction "2_2") (pintype "passive"))
    )
    (net (code "8") (name "/N_5") (class "Default")
      (node (ref "LED_1_5") (pin "C") (pinfunction "C_C") (pintype "passive"))
      (node (ref "LED_2_5") (pin "C") (pinfunction "C_C") (pintype "passive"))
      (node (ref "LED_3_5") (pin "C") (pinfunction "C_C") (pintype "passive"))
      (node (ref "LED_4_5") (pin "C") (pinfunction "C_C") (pintype "passive"))
      (node (ref "LED_5_1") (pin "A") (pinfunction "A_A") (pintype "passive"))
      (node (ref "LED_5_2") (pin "A") (pinfunction "A_A") (pintype "passive"))
      (node (ref "LED_5_3") (pin "A") (pinfunction "A_A") (pintype "passive"))
      (node (ref "LED_5_4") (pin "A") (pinfunction "A_A") (pintype "passive"))
      (node (ref "LED_5_6") (pin "A") (pinfunction "A_A") (pintype "passive"))
      (node (ref "LED_5_7") (pin "A") (pinfunction "A_A") (pintype "passive"))
      (node (ref "LED_5_8") (pin "A") (pinfunction "A_A") (pintype "passive"))
      (node (ref "LED_5_9") (pin "A") (pinfunction "A_A") (pintype "passive"))
      (node (ref "LED_6_5") (pin "C") (pinfunction "C_C") (pintype "passive"))
      (node (ref "LED_7_5") (pin "C") (pinfunction "C_C") (pintype "passive"))
      (node (ref "LED_8_5") (pin "C") (pinfunction "C_C") (pintype "passive"))
      (node (ref "LED_9_5_2") (pin "C") (pinfunction "C_C") (pintype "passive"))
      (node (ref "NPN5") (pin "E") (pinfunction "E_E") (pintype "passive"))
      (node (ref "RN5") (pin "2") (pinfunction "2_2") (pintype "passive"))
    )
    (net (code "9") (name "/N_6") (class "Default")
      (node (ref "LED_1_6") (pin "C") (pinfunction "C_C") (pintype "passive"))
      (node (ref "LED_2_6") (pin "C") (pinfunction "C_C") (pintype "passive"))
      (node (ref "LED_3_6") (pin "C") (pinfunction "C_C") (pintype "passive"))
      (node (ref "LED_4_6") (pin "C") (pinfunction "C_C") (pintype "passive"))
      (node (ref "LED_5_6") (pin "C") (pinfunction "C_C") (pintype "passive"))
      (node (ref "LED_6_1") (pin "A") (pinfunction "A_A") (pintype "passive"))
      (node (ref "LED_6_2") (pin "A") (pinfunction "A_A") (pintype "passive"))
      (node (ref "LED_6_3") (pin "A") (pinfunction "A_A") (pintype "passive"))
      (node (ref "LED_6_4") (pin "A") (pinfunction "A_A") (pintype "passive"))
      (node (ref "LED_6_5") (pin "A") (pinfunction "A_A") (pintype "passive"))
      (node (ref "LED_6_7") (pin "A") (pinfunction "A_A") (pintype "passive"))
      (node (ref "LED_6_8") (pin "A") (pinfunction "A_A") (pintype "passive"))
      (node (ref "LED_6_9") (pin "A") (pinfunction "A_A") (pintype "passive"))
      (node (ref "LED_7_6") (pin "C") (pinfunction "C_C") (pintype "passive"))
      (node (ref "LED_8_6") (pin "C") (pinfunction "C_C") (pintype "passive"))
      (node (ref "LED_9_6_2") (pin "C") (pinfunction "C_C") (pintype "passive"))
      (node (ref "NPN6") (pin "E") (pinfunction "E_E") (pintype "passive"))
      (node (ref "RN6") (pin "2") (pinfunction "2_2") (pintype "passive"))
    )
    (net (code "10") (name "/N_7") (class "Default")
      (node (ref "LED_1_7") (pin "C") (pinfunction "C_C") (pintype "passive"))
      (node (ref "LED_2_7") (pin "C") (pinfunction "C_C") (pintype "passive"))
      (node (ref "LED_3_7") (pin "C") (pinfunction "C_C") (pintype "passive"))
      (node (ref "LED_4_7") (pin "C") (pinfunction "C_C") (pintype "passive"))
      (node (ref "LED_5_7") (pin "C") (pinfunction "C_C") (pintype "passive"))
      (node (ref "LED_6_7") (pin "C") (pinfunction "C_C") (pintype "passive"))
      (node (ref "LED_7_1") (pin "A") (pinfunction "A_A") (pintype "passive"))
      (node (ref "LED_7_2") (pin "A") (pinfunction "A_A") (pintype "passive"))
      (node (ref "LED_7_3") (pin "A") (pinfunction "A_A") (pintype "passive"))
      (node (ref "LED_7_4") (pin "A") (pinfunction "A_A") (pintype "passive"))
      (node (ref "LED_7_5") (pin "A") (pinfunction "A_A") (pintype "passive"))
      (node (ref "LED_7_6") (pin "A") (pinfunction "A_A") (pintype "passive"))
      (node (ref "LED_7_8") (pin "A") (pinfunction "A_A") (pintype "passive"))
      (node (ref "LED_7_9") (pin "A") (pinfunction "A_A") (pintype "passive"))
      (node (ref "LED_8_7") (pin "C") (pinfunction "C_C") (pintype "passive"))
      (node (ref "LED_9_7_2") (pin "C") (pinfunction "C_C") (pintype "passive"))
      (node (ref "NPN7") (pin "E") (pinfunction "E_E") (pintype "passive"))
      (node (ref "RN7") (pin "2") (pinfunction "2_2") (pintype "passive"))
    )
    (net (code "11") (name "/N_8") (class "Default")
      (node (ref "LED_1_8") (pin "C") (pinfunction "C_C") (pintype "passive"))
      (node (ref "LED_2_8") (pin "C") (pinfunction "C_C") (pintype "passive"))
      (node (ref "LED_3_8") (pin "C") (pinfunction "C_C") (pintype "passive"))
      (node (ref "LED_4_8") (pin "C") (pinfunction "C_C") (pintype "passive"))
      (node (ref "LED_5_8") (pin "C") (pinfunction "C_C") (pintype "passive"))
      (node (ref "LED_6_8") (pin "C") (pinfunction "C_C") (pintype "passive"))
      (node (ref "LED_7_8") (pin "C") (pinfunction "C_C") (pintype "passive"))
      (node (ref "LED_8_1_1") (pin "A") (pinfunction "A_A") (pintype "passive"))
      (node (ref "LED_8_2_1") (pin "A") (pinfunction "A_A") (pintype "passive"))
      (node (ref "LED_8_3_1") (pin "A") (pinfunction "A_A") (pintype "passive"))
      (node (ref "LED_8_4_1") (pin "A") (pinfunction "A_A") (pintype "passive"))
      (node (ref "LED_8_5") (pin "A") (pinfunction "A_A") (pintype "passive"))
      (node (ref "LED_8_6") (pin "A") (pinfunction "A_A") (pintype "passive"))
      (node (ref "LED_8_7") (pin "A") (pinfunction "A_A") (pintype "passive"))
      (node (ref "LED_8_9") (pin "A") (pinfunction "A_A") (pintype "passive"))
      (node (ref "LED_9_8_2") (pin "C") (pinfunction "C_C") (pintype "passive"))
      (node (ref "NPN8") (pin "E") (pinfunction "E_E") (pintype "passive"))
      (node (ref "RN8") (pin "2") (pinfunction "2_2") (pintype "passive"))
    )
    (net (code "12") (name "/N_9") (class "Default")
      (node (ref "LED_1_9") (pin "C") (pinfunction "C_C") (pintype "passive"))
      (node (ref "LED_2_9") (pin "C") (pinfunction "C_C") (pintype "passive"))
      (node (ref "LED_3_9") (pin "C") (pinfunction "C_C") (pintype "passive"))
      (node (ref "LED_4_9") (pin "C") (pinfunction "C_C") (pintype "passive"))
      (node (ref "LED_5_9") (pin "C") (pinfunction "C_C") (pintype "passive"))
      (node (ref "LED_6_9") (pin "C") (pinfunction "C_C") (pintype "passive"))
      (node (ref "LED_7_9") (pin "C") (pinfunction "C_C") (pintype "passive"))
      (node (ref "LED_8_9") (pin "C") (pinfunction "C_C") (pintype "passive"))
      (node (ref "LED_9_1_1") (pin "A") (pinfunction "A_A") (pintype "passive"))
      (node (ref "LED_9_2_1") (pin "A") (pinfunction "A_A") (pintype "passive"))
      (node (ref "LED_9_3_1") (pin "A") (pinfunction "A_A") (pintype "passive"))
      (node (ref "LED_9_4_1") (pin "A") (pinfunction "A_A") (pintype "passive"))
      (node (ref "LED_9_5_1") (pin "A") (pinfunction "A_A") (pintype "passive"))
      (node (ref "LED_9_6_1") (pin "A") (pinfunction "A_A") (pintype "passive"))
      (node (ref "LED_9_7_1") (pin "A") (pinfunction "A_A") (pintype "passive"))
      (node (ref "LED_9_8_1") (pin "A") (pinfunction "A_A") (pintype "passive"))
      (node (ref "NPN9") (pin "E") (pinfunction "E_E") (pintype "passive"))
      (node (ref "RN9") (pin "2") (pinfunction "2_2") (pintype "passive"))
    )
    (net (code "13") (name "/PB0") (class "Default")
      (node (ref "CN9") (pin "1") (pinfunction "1_1") (pintype "passive"))
      (node (ref "IC2") (pin "12") (pinfunction "PB0(ICP1/CLKO/PCINT0)_12") (pintype "bidirectional"))
    )
    (net (code "14") (name "/PC0") (class "Default")
      (node (ref "IC2") (pin "23") (pinfunction "PC0(ADC0/PCINT8)_23") (pintype "bidirectional"))
      (node (ref "RR1") (pin "2") (pinfunction "2_2") (pintype "passive"))
    )
    (net (code "15") (name "/PC1") (class "Default")
      (node (ref "IC2") (pin "24") (pinfunction "PC1(ADC1/PCINT9)_24") (pintype "bidirectional"))
      (node (ref "RR2") (pin "2") (pinfunction "2_2") (pintype "passive"))
    )
    (net (code "16") (name "/PC2") (class "Default")
      (node (ref "IC2") (pin "25") (pinfunction "PC2(ADC2/PCINT10)_25") (pintype "bidirectional"))
      (node (ref "RR3") (pin "2") (pinfunction "2_2") (pintype "passive"))
    )
    (net (code "17") (name "/PC3") (class "Default")
      (node (ref "IC2") (pin "26") (pinfunction "PC3(ADC3/PCINT11)_26") (pintype "bidirectional"))
      (node (ref "RR4") (pin "2") (pinfunction "2_2") (pintype "passive"))
    )
    (net (code "18") (name "/PC4") (class "Default")
      (node (ref "IC2") (pin "27") (pinfunction "PC4(ADC4/SDA/PCINT12)_27") (pintype "bidirectional"))
      (node (ref "RR5") (pin "2") (pinfunction "2_2") (pintype "passive"))
    )
    (net (code "19") (name "/PC5") (class "Default")
      (node (ref "IC2") (pin "28") (pinfunction "PC5(ADC5/SCL/PCINT13)_28") (pintype "bidirectional"))
      (node (ref "RR6") (pin "2") (pinfunction "2_2") (pintype "passive"))
    )
    (net (code "20") (name "/PD0") (class "Default")
      (node (ref "CN1") (pin "1") (pinfunction "1_1") (pintype "passive"))
      (node (ref "IC2") (pin "30") (pinfunction "PD0(RXD/PCINT16)_30") (pintype "bidirectional"))
    )
    (net (code "21") (name "/PD1") (class "Default")
      (node (ref "CN2") (pin "1") (pinfunction "1_1") (pintype "passive"))
      (node (ref "IC2") (pin "31") (pinfunction "PD1(TXD/PCINT17)_31") (pintype "bidirectional"))
    )
    (net (code "22") (name "/PD2") (class "Default")
      (node (ref "CN3") (pin "1") (pinfunction "1_1") (pintype "passive"))
      (node (ref "IC2") (pin "32") (pinfunction "PD2(INT0/PCINT18)_32") (pintype "bidirectional"))
    )
    (net (code "23") (name "/PD3") (class "Default")
      (node (ref "CN4") (pin "1") (pinfunction "1_1") (pintype "passive"))
      (node (ref "IC2") (pin "1") (pinfunction "PD3(INT1/OC2B/PCINT19)_1") (pintype "bidirectional"))
    )
    (net (code "24") (name "/PD4") (class "Default")
      (node (ref "CN5") (pin "1") (pinfunction "1_1") (pintype "passive"))
      (node (ref "IC2") (pin "2") (pinfunction "PD4(T0/XCK/PCINT20)_2") (pintype "bidirectional"))
    )
    (net (code "25") (name "/PD5") (class "Default")
      (node (ref "CN6") (pin "1") (pinfunction "1_1") (pintype "passive"))
      (node (ref "IC2") (pin "9") (pinfunction "PD5(T1/OC0B/PCINT21)_9") (pintype "bidirectional"))
    )
    (net (code "26") (name "/PD6") (class "Default")
      (node (ref "CN7") (pin "1") (pinfunction "1_1") (pintype "passive"))
      (node (ref "IC2") (pin "10") (pinfunction "PD6(AIN0/OC0A/PCINT22)_10") (pintype "bidirectional"))
    )
    (net (code "27") (name "/PD7") (class "Default")
      (node (ref "CN8") (pin "1") (pinfunction "1_1") (pintype "passive"))
      (node (ref "IC2") (pin "11") (pinfunction "PD7(AIN1/PCINT23)_11") (pintype "bidirectional"))
    )
    (net (code "28") (name "/ROTOR1") (class "Default")
      (node (ref "RR1") (pin "1") (pinfunction "1_1") (pintype "passive"))
    )
    (net (code "29") (name "/ROTOR2") (class "Default")
      (node (ref "RR2") (pin "1") (pinfunction "1_1") (pintype "passive"))
    )
    (net (code "30") (name "/ROTOR3") (class "Default")
      (node (ref "RR3") (pin "1") (pinfunction "1_1") (pintype "passive"))
    )
    (net (code "31") (name "GND") (class "Default")
      (node (ref "C1") (pin "2") (pinfunction "2_2") (pintype "passive"))
      (node (ref "C2") (pin "2") (pinfunction "2_2") (pintype "passive"))
      (node (ref "C3") (pin "2") (pinfunction "2_2") (pintype "passive"))
      (node (ref "GND") (pin "TP") (pinfunction "TP_TP") (pintype "input"))
      (node (ref "GND2") (pin "TP") (pinfunction "TP_TP") (pintype "input"))
      (node (ref "IC2") (pin "21") (pinfunction "AGND_21") (pintype "power_in"))
      (node (ref "IC2") (pin "3") (pinfunction "GND_3") (pintype "power_in"))
      (node (ref "IC2") (pin "5") (pinfunction "GND_5") (pintype "power_in"))
      (node (ref "PNP1") (pin "C") (pinfunction "C_C") (pintype "passive"))
      (node (ref "PNP2") (pin "C") (pinfunction "C_C") (pintype "passive"))
      (node (ref "PNP3") (pin "C") (pinfunction "C_C") (pintype "passive"))
      (node (ref "PNP4") (pin "C") (pinfunction "C_C") (pintype "passive"))
      (node (ref "PNP5") (pin "C") (pinfunction "C_C") (pintype "passive"))
      (node (ref "PNP6") (pin "C") (pinfunction "C_C") (pintype "passive"))
      (node (ref "PNP7") (pin "C") (pinfunction "C_C") (pintype "passive"))
      (node (ref "PNP8") (pin "C") (pinfunction "C_C") (pintype "passive"))
      (node (ref "PNP9") (pin "C") (pinfunction "C_C") (pintype "passive"))
    )
    (net (code "32") (name "Net-(CN1-Pad2)") (class "Default")
      (node (ref "CN1") (pin "2") (pinfunction "2_2") (pintype "passive"))
      (node (ref "NPN1") (pin "B") (pinfunction "B_B") (pintype "passive"))
      (node (ref "PNP1") (pin "B") (pinfunction "B_B") (pintype "passive"))
    )
    (net (code "33") (name "Net-(CN2-Pad2)") (class "Default")
      (node (ref "CN2") (pin "2") (pinfunction "2_2") (pintype "passive"))
      (node (ref "NPN2") (pin "B") (pinfunction "B_B") (pintype "passive"))
      (node (ref "PNP2") (pin "B") (pinfunction "B_B") (pintype "passive"))
    )
    (net (code "34") (name "Net-(CN3-Pad2)") (class "Default")
      (node (ref "CN3") (pin "2") (pinfunction "2_2") (pintype "passive"))
      (node (ref "NPN3") (pin "B") (pinfunction "B_B") (pintype "passive"))
      (node (ref "PNP3") (pin "B") (pinfunction "B_B") (pintype "passive"))
    )
    (net (code "35") (name "Net-(CN4-Pad2)") (class "Default")
      (node (ref "CN4") (pin "2") (pinfunction "2_2") (pintype "passive"))
      (node (ref "NPN4") (pin "B") (pinfunction "B_B") (pintype "passive"))
      (node (ref "PNP4") (pin "B") (pinfunction "B_B") (pintype "passive"))
    )
    (net (code "36") (name "Net-(CN5-Pad2)") (class "Default")
      (node (ref "CN5") (pin "2") (pinfunction "2_2") (pintype "passive"))
      (node (ref "NPN5") (pin "B") (pinfunction "B_B") (pintype "passive"))
      (node (ref "PNP5") (pin "B") (pinfunction "B_B") (pintype "passive"))
    )
    (net (code "37") (name "Net-(CN6-Pad2)") (class "Default")
      (node (ref "CN6") (pin "2") (pinfunction "2_2") (pintype "passive"))
      (node (ref "NPN6") (pin "B") (pinfunction "B_B") (pintype "passive"))
      (node (ref "PNP6") (pin "B") (pinfunction "B_B") (pintype "passive"))
    )
    (net (code "38") (name "Net-(CN7-Pad2)") (class "Default")
      (node (ref "CN7") (pin "2") (pinfunction "2_2") (pintype "passive"))
      (node (ref "NPN7") (pin "B") (pinfunction "B_B") (pintype "passive"))
      (node (ref "PNP7") (pin "B") (pinfunction "B_B") (pintype "passive"))
    )
    (net (code "39") (name "Net-(CN8-Pad2)") (class "Default")
      (node (ref "CN8") (pin "2") (pinfunction "2_2") (pintype "passive"))
      (node (ref "NPN8") (pin "B") (pinfunction "B_B") (pintype "passive"))
      (node (ref "PNP8") (pin "B") (pinfunction "B_B") (pintype "passive"))
    )
    (net (code "40") (name "Net-(CN9-Pad2)") (class "Default")
      (node (ref "CN9") (pin "2") (pinfunction "2_2") (pintype "passive"))
      (node (ref "NPN9") (pin "B") (pinfunction "B_B") (pintype "passive"))
      (node (ref "PNP9") (pin "B") (pinfunction "B_B") (pintype "passive"))
    )
    (net (code "41") (name "Net-(IC2-PB3(MOSI{slash}OC2A{slash}PCINT3))") (class "Default")
      (node (ref "IC2") (pin "15") (pinfunction "PB3(MOSI/OC2A/PCINT3)_15") (pintype "bidirectional"))
      (node (ref "MOSI") (pin "TP") (pinfunction "TP_TP") (pintype "input"))
    )
    (net (code "42") (name "Net-(IC2-PB4(MISO{slash}PCINT4))") (class "Default")
      (node (ref "IC2") (pin "16") (pinfunction "PB4(MISO/PCINT4)_16") (pintype "bidirectional"))
      (node (ref "MISO") (pin "TP") (pinfunction "TP_TP") (pintype "input"))
    )
    (net (code "43") (name "Net-(IC2-PB5(SCK{slash}PCINT5))") (class "Default")
      (node (ref "IC2") (pin "17") (pinfunction "PB5(SCK/PCINT5)_17") (pintype "bidirectional"))
      (node (ref "SCK") (pin "TP") (pinfunction "TP_TP") (pintype "input"))
    )
    (net (code "44") (name "Net-(IC2-PB6(XTAL1{slash}TOSC1{slash}PCINT6))") (class "Default")
      (node (ref "C1") (pin "1") (pinfunction "1_1") (pintype "passive"))
      (node (ref "IC2") (pin "7") (pinfunction "PB6(XTAL1/TOSC1/PCINT6)_7") (pintype "bidirectional"))
      (node (ref "Q1") (pin "1") (pinfunction "1_1") (pintype "passive"))
    )
    (net (code "45") (name "Net-(IC2-PB7(XTAL2{slash}TOSC2{slash}PCINT7))") (class "Default")
      (node (ref "C2") (pin "1") (pinfunction "1_1") (pintype "passive"))
      (node (ref "IC2") (pin "8") (pinfunction "PB7(XTAL2/TOSC2/PCINT7)_8") (pintype "bidirectional"))
      (node (ref "Q1") (pin "3") (pinfunction "3_3") (pintype "passive"))
    )
    (net (code "46") (name "Net-(IC2-PC6({slash}RESET{slash}PCINT14))") (class "Default")
      (node (ref "IC2") (pin "29") (pinfunction "PC6(/RESET/PCINT14)_29") (pintype "bidirectional"))
      (node (ref "RESET") (pin "TP") (pinfunction "TP_TP") (pintype "input"))
    )
    (net (code "47") (name "Net-(LED_8_1_1-PadC)") (class "Default")
      (node (ref "LED_8_1_1") (pin "C") (pinfunction "C_C") (pintype "passive"))
      (node (ref "LED_8_1_2") (pin "A") (pinfunction "A_A") (pintype "passive"))
    )
    (net (code "48") (name "Net-(LED_8_2_1-PadC)") (class "Default")
      (node (ref "LED_8_2_1") (pin "C") (pinfunction "C_C") (pintype "passive"))
      (node (ref "LED_8_2_2") (pin "A") (pinfunction "A_A") (pintype "passive"))
    )
    (net (code "49") (name "Net-(LED_8_3_1-PadC)") (class "Default")
      (node (ref "LED_8_3_1") (pin "C") (pinfunction "C_C") (pintype "passive"))
      (node (ref "LED_8_3_2") (pin "A") (pinfunction "A_A") (pintype "passive"))
    )
    (net (code "50") (name "Net-(LED_8_4_1-PadC)") (class "Default")
      (node (ref "LED_8_4_1") (pin "C") (pinfunction "C_C") (pintype "passive"))
      (node (ref "LED_8_4_2") (pin "A") (pinfunction "A_A") (pintype "passive"))
    )
    (net (code "51") (name "Net-(LED_9_1_1-PadC)") (class "Default")
      (node (ref "LED_9_1_1") (pin "C") (pinfunction "C_C") (pintype "passive"))
      (node (ref "LED_9_1_2") (pin "A") (pinfunction "A_A") (pintype "passive"))
    )
    (net (code "52") (name "Net-(LED_9_2_1-PadC)") (class "Default")
      (node (ref "LED_9_2_1") (pin "C") (pinfunction "C_C") (pintype "passive"))
      (node (ref "LED_9_2_2") (pin "A") (pinfunction "A_A") (pintype "passive"))
    )
    (net (code "53") (name "Net-(LED_9_3_1-PadC)") (class "Default")
      (node (ref "LED_9_3_1") (pin "C") (pinfunction "C_C") (pintype "passive"))
      (node (ref "LED_9_3_2") (pin "A") (pinfunction "A_A") (pintype "passive"))
    )
    (net (code "54") (name "Net-(LED_9_4_1-PadC)") (class "Default")
      (node (ref "LED_9_4_1") (pin "C") (pinfunction "C_C") (pintype "passive"))
      (node (ref "LED_9_4_2") (pin "A") (pinfunction "A_A") (pintype "passive"))
    )
    (net (code "55") (name "Net-(LED_9_5_1-PadC)") (class "Default")
      (node (ref "LED_9_5_1") (pin "C") (pinfunction "C_C") (pintype "passive"))
      (node (ref "LED_9_5_2") (pin "A") (pinfunction "A_A") (pintype "passive"))
    )
    (net (code "56") (name "Net-(LED_9_6_1-PadC)") (class "Default")
      (node (ref "LED_9_6_1") (pin "C") (pinfunction "C_C") (pintype "passive"))
      (node (ref "LED_9_6_2") (pin "A") (pinfunction "A_A") (pintype "passive"))
    )
    (net (code "57") (name "Net-(LED_9_7_1-PadC)") (class "Default")
      (node (ref "LED_9_7_1") (pin "C") (pinfunction "C_C") (pintype "passive"))
      (node (ref "LED_9_7_2") (pin "A") (pinfunction "A_A") (pintype "passive"))
    )
    (net (code "58") (name "Net-(LED_9_8_1-PadC)") (class "Default")
      (node (ref "LED_9_8_1") (pin "C") (pinfunction "C_C") (pintype "passive"))
      (node (ref "LED_9_8_2") (pin "A") (pinfunction "A_A") (pintype "passive"))
    )
    (net (code "59") (name "Net-(PNP1-PadE)") (class "Default")
      (node (ref "PNP1") (pin "E") (pinfunction "E_E") (pintype "passive"))
      (node (ref "RN1") (pin "1") (pinfunction "1_1") (pintype "passive"))
    )
    (net (code "60") (name "Net-(PNP2-PadE)") (class "Default")
      (node (ref "PNP2") (pin "E") (pinfunction "E_E") (pintype "passive"))
      (node (ref "RN2") (pin "1") (pinfunction "1_1") (pintype "passive"))
    )
    (net (code "61") (name "Net-(PNP3-PadE)") (class "Default")
      (node (ref "PNP3") (pin "E") (pinfunction "E_E") (pintype "passive"))
      (node (ref "RN3") (pin "1") (pinfunction "1_1") (pintype "passive"))
    )
    (net (code "62") (name "Net-(PNP4-PadE)") (class "Default")
      (node (ref "PNP4") (pin "E") (pinfunction "E_E") (pintype "passive"))
      (node (ref "RN4") (pin "1") (pinfunction "1_1") (pintype "passive"))
    )
    (net (code "63") (name "Net-(PNP5-PadE)") (class "Default")
      (node (ref "PNP5") (pin "E") (pinfunction "E_E") (pintype "passive"))
      (node (ref "RN5") (pin "1") (pinfunction "1_1") (pintype "passive"))
    )
    (net (code "64") (name "Net-(PNP6-PadE)") (class "Default")
      (node (ref "PNP6") (pin "E") (pinfunction "E_E") (pintype "passive"))
      (node (ref "RN6") (pin "1") (pinfunction "1_1") (pintype "passive"))
    )
    (net (code "65") (name "Net-(PNP7-PadE)") (class "Default")
      (node (ref "PNP7") (pin "E") (pinfunction "E_E") (pintype "passive"))
      (node (ref "RN7") (pin "1") (pinfunction "1_1") (pintype "passive"))
    )
    (net (code "66") (name "Net-(PNP8-PadE)") (class "Default")
      (node (ref "PNP8") (pin "E") (pinfunction "E_E") (pintype "passive"))
      (node (ref "RN8") (pin "1") (pinfunction "1_1") (pintype "passive"))
    )
    (net (code "67") (name "Net-(PNP9-PadE)") (class "Default")
      (node (ref "PNP9") (pin "E") (pinfunction "E_E") (pintype "passive"))
      (node (ref "RN9") (pin "1") (pinfunction "1_1") (pintype "passive"))
    )
    (net (code "68") (name "VCC") (class "Default")
      (node (ref "C3") (pin "1") (pinfunction "1_1") (pintype "passive"))
      (node (ref "IC2") (pin "18") (pinfunction "AVCC_18") (pintype "passive"))
      (node (ref "IC2") (pin "4") (pinfunction "VCC_4") (pintype "power_in"))
      (node (ref "IC2") (pin "6") (pinfunction "VCC_6") (pintype "power_in"))
      (node (ref "NPN1") (pin "C") (pinfunction "C_C") (pintype "passive"))
      (node (ref "NPN2") (pin "C") (pinfunction "C_C") (pintype "passive"))
      (node (ref "NPN3") (pin "C") (pinfunction "C_C") (pintype "passive"))
      (node (ref "NPN4") (pin "C") (pinfunction "C_C") (pintype "passive"))
      (node (ref "NPN5") (pin "C") (pinfunction "C_C") (pintype "passive"))
      (node (ref "NPN6") (pin "C") (pinfunction "C_C") (pintype "passive"))
      (node (ref "NPN7") (pin "C") (pinfunction "C_C") (pintype "passive"))
      (node (ref "NPN8") (pin "C") (pinfunction "C_C") (pintype "passive"))
      (node (ref "NPN9") (pin "C") (pinfunction "C_C") (pintype "passive"))
      (node (ref "V+") (pin "TP") (pinfunction "TP_TP") (pintype "input"))
      (node (ref "VCC") (pin "TP") (pinfunction "TP_TP") (pintype "input"))
    )
    (net (code "69") (name "unconnected-(IC2-ADC6-Pad19)") (class "Default")
      (node (ref "IC2") (pin "19") (pinfunction "ADC6_19") (pintype "passive"))
    )
    (net (code "70") (name "unconnected-(IC2-ADC7-Pad22)") (class "Default")
      (node (ref "IC2") (pin "22") (pinfunction "ADC7_22") (pintype "passive"))
    )
    (net (code "71") (name "unconnected-(IC2-AREF-Pad20)") (class "Default")
      (node (ref "IC2") (pin "20") (pinfunction "AREF_20") (pintype "passive"))
    )
    (net (code "72") (name "unconnected-(IC2-PB1(OC1A{slash}PCINT1)-Pad13)") (class "Default")
      (node (ref "IC2") (pin "13") (pinfunction "PB1(OC1A/PCINT1)_13") (pintype "bidirectional"))
    )
    (net (code "73") (name "unconnected-(IC2-PB2(SS{slash}OC1B{slash}PCINT2)-Pad14)") (class "Default")
      (node (ref "IC2") (pin "14") (pinfunction "PB2(SS/OC1B/PCINT2)_14") (pintype "bidirectional"))
    )
    (net (code "74") (name "unconnected-(Q1-Pad2)") (class "Default")
      (node (ref "Q1") (pin "2") (pinfunction "2_2") (pintype "passive"))
    )
    (net (code "75") (name "unconnected-(Q1-Pad4)") (class "Default")
      (node (ref "Q1") (pin "4") (pinfunction "4_4") (pintype "passive"))
    )
  )
)
